# Generic_Electronics_Board_PCB_B.net
KiCad netlist of a schematic drawn in EAGLE
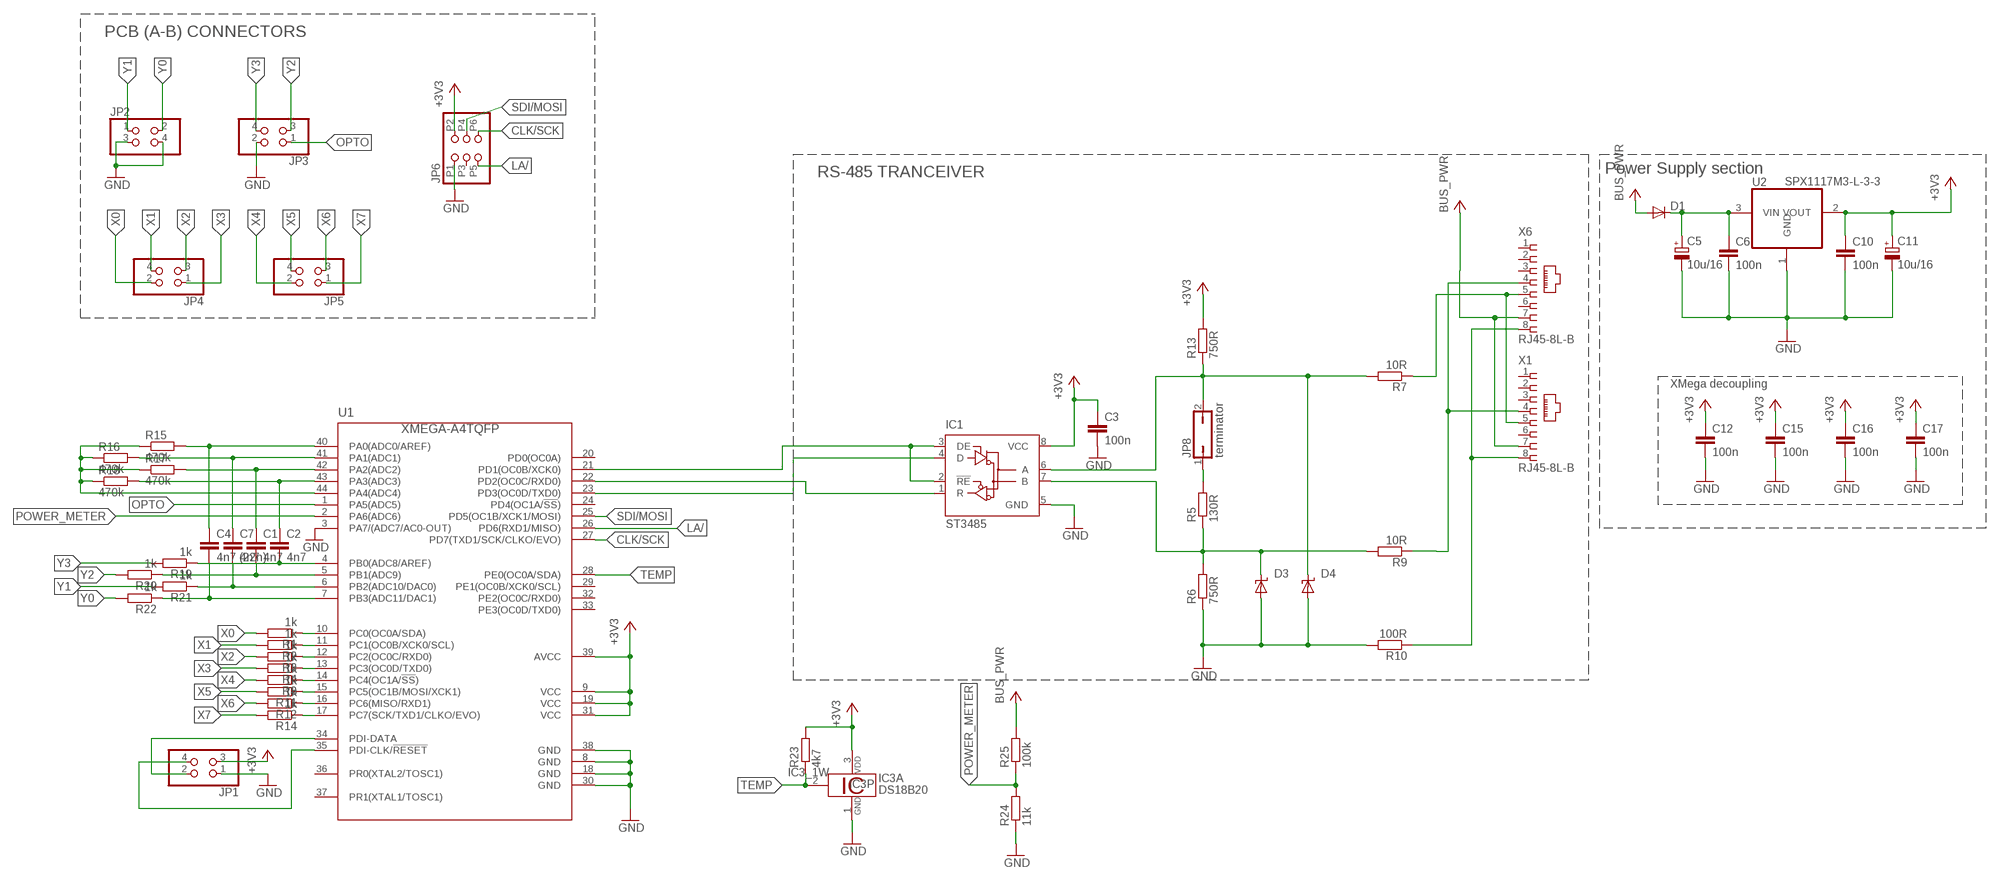
[diagram p0: schematic, sheet 1]

(export (version "E")
  (design (tool "Eeschema 10.0.6"))
  (components
    (comp (ref "C1")
      (value "4n7")
      (footprint "eagle-import:C0603")
      (libsource (lib "eagle-import") (part "C-EUC0603"))
    )
    (comp (ref "C2")
      (value "4n7")
      (footprint "eagle-import:C0603")
      (libsource (lib "eagle-import") (part "C-EUC0603"))
    )
    (comp (ref "C3")
      (value "100n")
      (footprint "eagle-import:C0603")
      (libsource (lib "eagle-import") (part "C-EUC0603"))
    )
    (comp (ref "C4")
      (value "4n7 (22n)")
      (footprint "eagle-import:C0603")
      (libsource (lib "eagle-import") (part "C-EUC0603"))
    )
    (comp (ref "C5")
      (value "10u/16")
      (footprint "eagle-import:SMC_C")
      (libsource (lib "eagle-import") (part "CPOL-EUSMCC"))
    )
    (comp (ref "C6")
      (value "100n")
      (footprint "eagle-import:C0603")
      (libsource (lib "eagle-import") (part "C-EUC0603"))
    )
    (comp (ref "C7")
      (value "4n7")
      (footprint "eagle-import:C0603")
      (libsource (lib "eagle-import") (part "C-EUC0603"))
    )
    (comp (ref "C10")
      (value "100n")
      (footprint "eagle-import:C0603")
      (libsource (lib "eagle-import") (part "C-EUC0603"))
    )
    (comp (ref "C11")
      (value "10u/16")
      (footprint "eagle-import:SMC_C")
      (libsource (lib "eagle-import") (part "CPOL-EUSMCC"))
    )
    (comp (ref "C12")
      (value "100n")
      (footprint "eagle-import:C0603")
      (libsource (lib "eagle-import") (part "C-EUC0603"))
    )
    (comp (ref "C15")
      (value "100n")
      (footprint "eagle-import:C0603")
      (libsource (lib "eagle-import") (part "C-EUC0603"))
    )
    (comp (ref "C16")
      (value "100n")
      (footprint "eagle-import:C0603")
      (libsource (lib "eagle-import") (part "C-EUC0603"))
    )
    (comp (ref "C17")
      (value "100n")
      (footprint "eagle-import:C0603")
      (libsource (lib "eagle-import") (part "C-EUC0603"))
    )
    (comp (ref "D1")
      (value "DIODE-DO-214AC")
      (footprint "eagle-import:DO-214AC")
      (libsource (lib "eagle-import") (part "DIODE-DO-214AC"))
    )
    (comp (ref "D3")
      (value "SUPPRESSOR-SMBJ")
      (footprint "eagle-import:SMBJ")
      (libsource (lib "eagle-import") (part "SUPPRESSOR-SMBJ"))
    )
    (comp (ref "D4")
      (value "SUPPRESSOR-SMBJ")
      (footprint "eagle-import:SMBJ")
      (libsource (lib "eagle-import") (part "SUPPRESSOR-SMBJ"))
    )
    (comp (ref "IC1")
      (value "ST3485")
      (footprint "eagle-import:D_R-PDSO-G8")
      (libsource (lib "eagle-import") (part "75176AD"))
    )
    (comp (ref "IC3")
      (value "DS18B20")
      (footprint "eagle-import:TO92-")
      (libsource (lib "eagle-import") (part "DS18B20"))
    )
    (comp (ref "JP1")
      (value "PINHD-2X2SMD")
      (footprint "eagle-import:2X2SMD")
      (libsource (lib "eagle-import") (part "PINHD-2X2SMD"))
    )
    (comp (ref "JP2")
      (value "PINHD-2X2")
      (footprint "eagle-import:2X02")
      (libsource (lib "eagle-import") (part "PINHD-2X2"))
    )
    (comp (ref "JP3")
      (value "PINHD-2X2")
      (footprint "eagle-import:2X02")
      (libsource (lib "eagle-import") (part "PINHD-2X2"))
    )
    (comp (ref "JP4")
      (value "PINHD-2X2")
      (footprint "eagle-import:2X02")
      (libsource (lib "eagle-import") (part "PINHD-2X2"))
    )
    (comp (ref "JP5")
      (value "PINHD-2X2")
      (footprint "eagle-import:2X02")
      (libsource (lib "eagle-import") (part "PINHD-2X2"))
    )
    (comp (ref "JP6")
      (value "PINHD-2X3SMD")
      (footprint "eagle-import:2X3SMD")
      (libsource (lib "eagle-import") (part "PINHD-2X3SMD"))
    )
    (comp (ref "JP8")
      (value "terminator")
      (footprint "eagle-import:JP1")
      (libsource (lib "eagle-import") (part "JP1Q"))
    )
    (comp (ref "R1")
      (value "1k")
      (footprint "eagle-import:R0603")
      (libsource (lib "eagle-import") (part "R-EU_R0603"))
    )
    (comp (ref "R2")
      (value "1k")
      (footprint "eagle-import:R0603")
      (libsource (lib "eagle-import") (part "R-EU_R0603"))
    )
    (comp (ref "R3")
      (value "1k")
      (footprint "eagle-import:R0603")
      (libsource (lib "eagle-import") (part "R-EU_R0603"))
    )
    (comp (ref "R4")
      (value "1k")
      (footprint "eagle-import:R0603")
      (libsource (lib "eagle-import") (part "R-EU_R0603"))
    )
    (comp (ref "R5")
      (value "130R")
      (footprint "eagle-import:R0603")
      (libsource (lib "eagle-import") (part "R-EU_R0603"))
    )
    (comp (ref "R6")
      (value "750R")
      (footprint "eagle-import:R0603")
      (libsource (lib "eagle-import") (part "R-EU_R0603"))
    )
    (comp (ref "R7")
      (value "10R")
      (footprint "eagle-import:R0603")
      (libsource (lib "eagle-import") (part "R-EU_R0603"))
    )
    (comp (ref "R8")
      (value "1k")
      (footprint "eagle-import:R0603")
      (libsource (lib "eagle-import") (part "R-EU_R0603"))
    )
    (comp (ref "R9")
      (value "10R")
      (footprint "eagle-import:R0603")
      (libsource (lib "eagle-import") (part "R-EU_R0603"))
    )
    (comp (ref "R10")
      (value "100R")
      (footprint "eagle-import:R0603")
      (libsource (lib "eagle-import") (part "R-EU_R0603"))
    )
    (comp (ref "R11")
      (value "1k")
      (footprint "eagle-import:R0603")
      (libsource (lib "eagle-import") (part "R-EU_R0603"))
    )
    (comp (ref "R12")
      (value "1k")
      (footprint "eagle-import:R0603")
      (libsource (lib "eagle-import") (part "R-EU_R0603"))
    )
    (comp (ref "R13")
      (value "750R")
      (footprint "eagle-import:R0603")
      (libsource (lib "eagle-import") (part "R-EU_R0603"))
    )
    (comp (ref "R14")
      (value "1k")
      (footprint "eagle-import:R0603")
      (libsource (lib "eagle-import") (part "R-EU_R0603"))
    )
    (comp (ref "R15")
      (value "470k")
      (footprint "eagle-import:R0603")
      (libsource (lib "eagle-import") (part "R-EU_R0603"))
    )
    (comp (ref "R16")
      (value "470k")
      (footprint "eagle-import:R0603")
      (libsource (lib "eagle-import") (part "R-EU_R0603"))
    )
    (comp (ref "R17")
      (value "470k")
      (footprint "eagle-import:R0603")
      (libsource (lib "eagle-import") (part "R-EU_R0603"))
    )
    (comp (ref "R18")
      (value "470k")
      (footprint "eagle-import:R0603")
      (libsource (lib "eagle-import") (part "R-EU_R0603"))
    )
    (comp (ref "R19")
      (value "1k")
      (footprint "eagle-import:R0603")
      (libsource (lib "eagle-import") (part "R-EU_R0603"))
    )
    (comp (ref "R20")
      (value "1k")
      (footprint "eagle-import:R0603")
      (libsource (lib "eagle-import") (part "R-EU_R0603"))
    )
    (comp (ref "R21")
      (value "1k")
      (footprint "eagle-import:R0603")
      (libsource (lib "eagle-import") (part "R-EU_R0603"))
    )
    (comp (ref "R22")
      (value "1k")
      (footprint "eagle-import:R0603")
      (libsource (lib "eagle-import") (part "R-EU_R0603"))
    )
    (comp (ref "R23")
      (value "4k7")
      (footprint "eagle-import:R0603")
      (libsource (lib "eagle-import") (part "R-EU_R0603"))
    )
    (comp (ref "R24")
      (value "11k")
      (footprint "eagle-import:R0603")
      (libsource (lib "eagle-import") (part "R-EU_R0603"))
    )
    (comp (ref "R25")
      (value "100k")
      (footprint "eagle-import:R0603")
      (libsource (lib "eagle-import") (part "R-EU_R0603"))
    )
    (comp (ref "U1")
      (value "XMEGA-A4TQFP")
      (footprint "eagle-import:TQFP44")
      (libsource (lib "eagle-import") (part "XMEGA-A4TQFP"))
    )
    (comp (ref "U2")
      (value "SPX1117M3-L-3-3")
      (footprint "eagle-import:SOT223")
      (fields (field (name "MPN") "REG1117"))
      (libsource (lib "eagle-import") (part "REG1117"))
    )
    (comp (ref "X1")
      (value "RJ45-8L-B")
      (footprint "eagle-import:RJ45-NO-SHIELD")
      (fields
        (field (name "MF") "TYCO ELECTRONICS")
        (field (name "MF_1") "TYCO ELECTRONICS")
        (field (name "MPN") "RJ45-8L-B")
        (field (name "OC_FARNELL") "1279843")
        (field (name "OC_NEWARK") "52K4445")
      )
      (libsource (lib "eagle-import") (part "RJ45-8L-B"))
    )
    (comp (ref "X6")
      (value "RJ45-8L-B")
      (footprint "eagle-import:RJ45-NO-SHIELD")
      (fields (field (name "MF") "TYCO ELECTRONICS"))
      (libsource (lib "eagle-import") (part "RJ45-8L-B"))
    )
  )
  (nets
    (net (code "1") (name "+3V3") (class "Default")
      (node (ref "C10") (pin "1") (pinfunction "1_1") (pintype "passive"))
      (node (ref "C11") (pin "+") (pinfunction "+_+") (pintype "passive"))
      (node (ref "C12") (pin "1") (pinfunction "1_1") (pintype "passive"))
      (node (ref "C15") (pin "1") (pinfunction "1_1") (pintype "passive"))
      (node (ref "C16") (pin "1") (pinfunction "1_1") (pintype "passive"))
      (node (ref "C17") (pin "1") (pinfunction "1_1") (pintype "passive"))
      (node (ref "C3") (pin "1") (pinfunction "1_1") (pintype "passive"))
      (node (ref "IC1") (pin "8") (pinfunction "VCC_8") (pintype "power_in"))
      (node (ref "IC3") (pin "3") (pinfunction "VDD_3") (pintype "power_in"))
      (node (ref "JP1") (pin "3") (pinfunction "3_3") (pintype "passive"))
      (node (ref "JP6") (pin "P2") (pinfunction "2_P2") (pintype "passive"))
      (node (ref "R13") (pin "2") (pinfunction "2_2") (pintype "passive"))
      (node (ref "R23") (pin "2") (pinfunction "2_2") (pintype "passive"))
      (node (ref "U1") (pin "19") (pinfunction "VCC_19") (pintype "power_in"))
      (node (ref "U1") (pin "31") (pinfunction "VCC_31") (pintype "power_in"))
      (node (ref "U1") (pin "39") (pinfunction "AVCC_39") (pintype "power_in"))
      (node (ref "U1") (pin "9") (pinfunction "VCC_9") (pintype "power_in"))
      (node (ref "U2") (pin "2") (pinfunction "VOUT_2") (pintype "output"))
    )
    (net (code "2") (name "BUS_PWR") (class "Default")
      (node (ref "D1") (pin "A") (pinfunction "A_A") (pintype "passive"))
      (node (ref "R25") (pin "2") (pinfunction "2_2") (pintype "passive"))
      (node (ref "X1") (pin "7") (pinfunction "7_7") (pintype "passive"))
      (node (ref "X6") (pin "7") (pinfunction "7_7") (pintype "passive"))
    )
    (net (code "3") (name "CLK{slash}SCK") (class "Default")
      (node (ref "JP6") (pin "P6") (pinfunction "6_P6") (pintype "passive"))
      (node (ref "U1") (pin "27") (pinfunction "PD7(TXD1/SCK/CLKO/EVO)_27") (pintype "bidirectional"))
    )
    (net (code "4") (name "GND") (class "Default")
      (node (ref "C10") (pin "2") (pinfunction "2_2") (pintype "passive"))
      (node (ref "C11") (pin "-") (pinfunction "-_-") (pintype "passive"))
      (node (ref "C12") (pin "2") (pinfunction "2_2") (pintype "passive"))
      (node (ref "C15") (pin "2") (pinfunction "2_2") (pintype "passive"))
      (node (ref "C16") (pin "2") (pinfunction "2_2") (pintype "passive"))
      (node (ref "C17") (pin "2") (pinfunction "2_2") (pintype "passive"))
      (node (ref "C3") (pin "2") (pinfunction "2_2") (pintype "passive"))
      (node (ref "C5") (pin "-") (pinfunction "-_-") (pintype "passive"))
      (node (ref "C6") (pin "2") (pinfunction "2_2") (pintype "passive"))
      (node (ref "D3") (pin "A") (pinfunction "A_A") (pintype "passive"))
      (node (ref "D4") (pin "A") (pinfunction "A_A") (pintype "passive"))
      (node (ref "IC1") (pin "5") (pinfunction "GND_5") (pintype "power_in"))
      (node (ref "IC3") (pin "1") (pinfunction "GND_1") (pintype "power_in"))
      (node (ref "JP1") (pin "1") (pinfunction "1_1") (pintype "passive"))
      (node (ref "JP2") (pin "3") (pinfunction "3_3") (pintype "passive"))
      (node (ref "JP2") (pin "4") (pinfunction "4_4") (pintype "passive"))
      (node (ref "JP3") (pin "2") (pinfunction "2_2") (pintype "passive"))
      (node (ref "JP6") (pin "P1") (pinfunction "1_P1") (pintype "passive"))
      (node (ref "R10") (pin "2") (pinfunction "2_2") (pintype "passive"))
      (node (ref "R24") (pin "1") (pinfunction "1_1") (pintype "passive"))
      (node (ref "R6") (pin "1") (pinfunction "1_1") (pintype "passive"))
      (node (ref "U1") (pin "18") (pinfunction "GND_18") (pintype "power_in"))
      (node (ref "U1") (pin "3") (pinfunction "PA7/(ADC7/AC0-OUT)_3") (pintype "bidirectional"))
      (node (ref "U1") (pin "30") (pinfunction "GND_30") (pintype "power_in"))
      (node (ref "U1") (pin "38") (pinfunction "GND_38") (pintype "power_in"))
      (node (ref "U1") (pin "8") (pinfunction "GND_8") (pintype "power_in"))
      (node (ref "U2") (pin "1") (pinfunction "GND_1") (pintype "power_in"))
    )
    (net (code "5") (name "LA{slash}") (class "Default")
      (node (ref "JP6") (pin "P5") (pinfunction "5_P5") (pintype "passive"))
      (node (ref "U1") (pin "26") (pinfunction "PD6(RXD1/MISO)_26") (pintype "bidirectional"))
    )
    (net (code "6") (name "Net-(IC1-A)") (class "Default")
      (node (ref "D4") (pin "C") (pinfunction "C_C") (pintype "passive"))
      (node (ref "IC1") (pin "6") (pinfunction "A_6") (pintype "output"))
      (node (ref "JP8") (pin "2") (pinfunction "2_2") (pintype "passive"))
      (node (ref "R13") (pin "1") (pinfunction "1_1") (pintype "passive"))
      (node (ref "R7") (pin "2") (pinfunction "2_2") (pintype "passive"))
    )
    (net (code "7") (name "Net-(IC1-B)") (class "Default")
      (node (ref "D3") (pin "C") (pinfunction "C_C") (pintype "passive"))
      (node (ref "IC1") (pin "7") (pinfunction "B_7") (pintype "output"))
      (node (ref "R5") (pin "1") (pinfunction "1_1") (pintype "passive"))
      (node (ref "R6") (pin "2") (pinfunction "2_2") (pintype "passive"))
      (node (ref "R9") (pin "2") (pinfunction "2_2") (pintype "passive"))
    )
    (net (code "8") (name "Net-(IC1-D)") (class "Default")
      (node (ref "IC1") (pin "4") (pinfunction "D_4") (pintype "input"))
      (node (ref "U1") (pin "23") (pinfunction "PD3(OC0D/TXD0)_23") (pintype "bidirectional"))
    )
    (net (code "9") (name "Net-(IC1-DE)") (class "Default")
      (node (ref "IC1") (pin "2") (pinfunction "~{RE}_2") (pintype "input"))
      (node (ref "IC1") (pin "3") (pinfunction "DE_3") (pintype "input"))
      (node (ref "U1") (pin "21") (pinfunction "PD1(OC0B/XCK0)_21") (pintype "bidirectional"))
    )
    (net (code "10") (name "Net-(IC1-R)") (class "Default")
      (node (ref "IC1") (pin "1") (pinfunction "R_1") (pintype "input"))
      (node (ref "U1") (pin "22") (pinfunction "PD2(OC0C/RXD0)_22") (pintype "bidirectional"))
    )
    (net (code "11") (name "Net-(JP8-Pad1)") (class "Default")
      (node (ref "JP8") (pin "1") (pinfunction "1_1") (pintype "passive"))
      (node (ref "R5") (pin "2") (pinfunction "2_2") (pintype "passive"))
    )
    (net (code "12") (name "Net-(R7-Pad1)") (class "Default")
      (node (ref "R7") (pin "1") (pinfunction "1_1") (pintype "passive"))
      (node (ref "X1") (pin "5") (pinfunction "5_5") (pintype "passive"))
      (node (ref "X6") (pin "5") (pinfunction "5_5") (pintype "passive"))
    )
    (net (code "13") (name "Net-(R9-Pad1)") (class "Default")
      (node (ref "R9") (pin "1") (pinfunction "1_1") (pintype "passive"))
      (node (ref "X1") (pin "4") (pinfunction "4_4") (pintype "passive"))
      (node (ref "X6") (pin "4") (pinfunction "4_4") (pintype "passive"))
    )
    (net (code "14") (name "Net-(R10-Pad1)") (class "Default")
      (node (ref "R10") (pin "1") (pinfunction "1_1") (pintype "passive"))
      (node (ref "X1") (pin "8") (pinfunction "8_8") (pintype "passive"))
      (node (ref "X6") (pin "8") (pinfunction "8_8") (pintype "passive"))
    )
    (net (code "15") (name "Net-(U1-PA0(ADC0{slash}AREF))") (class "Default")
      (node (ref "C4") (pin "1") (pinfunction "1_1") (pintype "passive"))
      (node (ref "R15") (pin "2") (pinfunction "2_2") (pintype "passive"))
      (node (ref "U1") (pin "40") (pinfunction "PA0(ADC0/AREF)_40") (pintype "bidirectional"))
    )
    (net (code "16") (name "Net-(U1-PA1(ADC1))") (class "Default")
      (node (ref "C7") (pin "1") (pinfunction "1_1") (pintype "passive"))
      (node (ref "R16") (pin "2") (pinfunction "2_2") (pintype "passive"))
      (node (ref "U1") (pin "41") (pinfunction "PA1(ADC1)_41") (pintype "bidirectional"))
    )
    (net (code "17") (name "Net-(U1-PA2(ADC2))") (class "Default")
      (node (ref "C1") (pin "1") (pinfunction "1_1") (pintype "passive"))
      (node (ref "R17") (pin "2") (pinfunction "2_2") (pintype "passive"))
      (node (ref "U1") (pin "42") (pinfunction "PA2(ADC2)_42") (pintype "bidirectional"))
    )
    (net (code "18") (name "Net-(U1-PA3(ADC3))") (class "Default")
      (node (ref "C2") (pin "1") (pinfunction "1_1") (pintype "passive"))
      (node (ref "R18") (pin "2") (pinfunction "2_2") (pintype "passive"))
      (node (ref "U1") (pin "43") (pinfunction "PA3(ADC3)_43") (pintype "bidirectional"))
    )
    (net (code "19") (name "Net-(U1-PA4(ADC4))") (class "Default")
      (node (ref "R15") (pin "1") (pinfunction "1_1") (pintype "passive"))
      (node (ref "R16") (pin "1") (pinfunction "1_1") (pintype "passive"))
      (node (ref "R17") (pin "1") (pinfunction "1_1") (pintype "passive"))
      (node (ref "R18") (pin "1") (pinfunction "1_1") (pintype "passive"))
      (node (ref "U1") (pin "44") (pinfunction "PA4(ADC4)_44") (pintype "bidirectional"))
    )
    (net (code "20") (name "Net-(U1-PB0(ADC8{slash}AREF))") (class "Default")
      (node (ref "C2") (pin "2") (pinfunction "2_2") (pintype "passive"))
      (node (ref "R19") (pin "1") (pinfunction "1_1") (pintype "passive"))
      (node (ref "U1") (pin "4") (pinfunction "PB0(ADC8/AREF)_4") (pintype "bidirectional"))
    )
    (net (code "21") (name "Net-(U1-PB1(ADC9))") (class "Default")
      (node (ref "C1") (pin "2") (pinfunction "2_2") (pintype "passive"))
      (node (ref "R20") (pin "1") (pinfunction "1_1") (pintype "passive"))
      (node (ref "U1") (pin "5") (pinfunction "PB1(ADC9)_5") (pintype "bidirectional"))
    )
    (net (code "22") (name "Net-(U1-PB2(ADC10{slash}DAC0))") (class "Default")
      (node (ref "C7") (pin "2") (pinfunction "2_2") (pintype "passive"))
      (node (ref "R21") (pin "1") (pinfunction "1_1") (pintype "passive"))
      (node (ref "U1") (pin "6") (pinfunction "PB2(ADC10/DAC0)_6") (pintype "bidirectional"))
    )
    (net (code "23") (name "Net-(U1-PB3(ADC11{slash}DAC1))") (class "Default")
      (node (ref "C4") (pin "2") (pinfunction "2_2") (pintype "passive"))
      (node (ref "R22") (pin "1") (pinfunction "1_1") (pintype "passive"))
      (node (ref "U1") (pin "7") (pinfunction "PB3(ADC11/DAC1)_7") (pintype "bidirectional"))
    )
    (net (code "24") (name "Net-(U1-PC0(OC0A{slash}SDA))") (class "Default")
      (node (ref "R1") (pin "1") (pinfunction "1_1") (pintype "passive"))
      (node (ref "U1") (pin "10") (pinfunction "PC0(OC0A/SDA)_10") (pintype "bidirectional"))
    )
    (net (code "25") (name "Net-(U1-PC1(OC0B{slash}XCK0{slash}SCL))") (class "Default")
      (node (ref "R2") (pin "1") (pinfunction "1_1") (pintype "passive"))
      (node (ref "U1") (pin "11") (pinfunction "PC1(OC0B/XCK0/SCL)_11") (pintype "bidirectional"))
    )
    (net (code "26") (name "Net-(U1-PC2(OC0C{slash}RXD0))") (class "Default")
      (node (ref "R3") (pin "1") (pinfunction "1_1") (pintype "passive"))
      (node (ref "U1") (pin "12") (pinfunction "PC2(OC0C/RXD0)_12") (pintype "bidirectional"))
    )
    (net (code "27") (name "Net-(U1-PC3(OC0D{slash}TXD0))") (class "Default")
      (node (ref "R4") (pin "1") (pinfunction "1_1") (pintype "passive"))
      (node (ref "U1") (pin "13") (pinfunction "PC3(OC0D/TXD0)_13") (pintype "bidirectional"))
    )
    (net (code "28") (name "Net-(U1-PC4(OC1A{slash}~{SS}))") (class "Default")
      (node (ref "R8") (pin "1") (pinfunction "1_1") (pintype "passive"))
      (node (ref "U1") (pin "14") (pinfunction "PC4(OC1A/~{SS})_14") (pintype "bidirectional"))
    )
    (net (code "29") (name "Net-(U1-PC5(OC1B{slash}MOSI{slash}XCK1))") (class "Default")
      (node (ref "R11") (pin "1") (pinfunction "1_1") (pintype "passive"))
      (node (ref "U1") (pin "15") (pinfunction "PC5(OC1B/MOSI/XCK1)_15") (pintype "bidirectional"))
    )
    (net (code "30") (name "Net-(U1-PC6(MISO{slash}RXD1))") (class "Default")
      (node (ref "R12") (pin "1") (pinfunction "1_1") (pintype "passive"))
      (node (ref "U1") (pin "16") (pinfunction "PC6(MISO/RXD1)_16") (pintype "bidirectional"))
    )
    (net (code "31") (name "Net-(U1-PC7(SCK{slash}TXD1{slash}CLKO{slash}EVO))") (class "Default")
      (node (ref "R14") (pin "1") (pinfunction "1_1") (pintype "passive"))
      (node (ref "U1") (pin "17") (pinfunction "PC7(SCK/TXD1/CLKO/EVO)_17") (pintype "bidirectional"))
    )
    (net (code "32") (name "Net-(U1-PDI-CLK{slash}~{RESET})") (class "Default")
      (node (ref "JP1") (pin "4") (pinfunction "4_4") (pintype "passive"))
      (node (ref "U1") (pin "35") (pinfunction "PDI-CLK/~{RESET}_35") (pintype "input"))
    )
    (net (code "33") (name "Net-(U1-PDI-DATA)") (class "Default")
      (node (ref "JP1") (pin "2") (pinfunction "2_2") (pintype "passive"))
      (node (ref "U1") (pin "34") (pinfunction "PDI-DATA_34") (pintype "bidirectional"))
    )
    (net (code "34") (name "Net-(U2-VIN)") (class "Default")
      (node (ref "C5") (pin "+") (pinfunction "+_+") (pintype "passive"))
      (node (ref "C6") (pin "1") (pinfunction "1_1") (pintype "passive"))
      (node (ref "D1") (pin "C") (pinfunction "C_C") (pintype "passive"))
      (node (ref "U2") (pin "3") (pinfunction "VIN_3") (pintype "input"))
    )
    (net (code "35") (name "OPTO") (class "Default")
      (node (ref "JP3") (pin "1") (pinfunction "1_1") (pintype "passive"))
      (node (ref "U1") (pin "1") (pinfunction "PA5(ADC5)_1") (pintype "bidirectional"))
    )
    (net (code "36") (name "POWER_METER") (class "Default")
      (node (ref "R24") (pin "2") (pinfunction "2_2") (pintype "passive"))
      (node (ref "R25") (pin "1") (pinfunction "1_1") (pintype "passive"))
      (node (ref "U1") (pin "2") (pinfunction "PA6(ADC6)_2") (pintype "bidirectional"))
    )
    (net (code "37") (name "SDI{slash}MOSI") (class "Default")
      (node (ref "JP6") (pin "P4") (pinfunction "4_P4") (pintype "passive"))
      (node (ref "U1") (pin "25") (pinfunction "PD5(OC1B/XCK1/MOSI)_25") (pintype "bidirectional"))
    )
    (net (code "38") (name "TEMP") (class "Default")
      (node (ref "IC3") (pin "2") (pinfunction "1W_2") (pintype "power_in"))
      (node (ref "R23") (pin "1") (pinfunction "1_1") (pintype "passive"))
      (node (ref "U1") (pin "28") (pinfunction "PE0(OC0A/SDA)_28") (pintype "bidirectional"))
    )
    (net (code "39") (name "X0") (class "Default")
      (node (ref "JP4") (pin "2") (pinfunction "2_2") (pintype "passive"))
      (node (ref "R1") (pin "2") (pinfunction "2_2") (pintype "passive"))
    )
    (net (code "40") (name "X1") (class "Default")
      (node (ref "JP4") (pin "4") (pinfunction "4_4") (pintype "passive"))
      (node (ref "R2") (pin "2") (pinfunction "2_2") (pintype "passive"))
    )
    (net (code "41") (name "X2") (class "Default")
      (node (ref "JP4") (pin "3") (pinfunction "3_3") (pintype "passive"))
      (node (ref "R3") (pin "2") (pinfunction "2_2") (pintype "passive"))
    )
    (net (code "42") (name "X3") (class "Default")
      (node (ref "JP4") (pin "1") (pinfunction "1_1") (pintype "passive"))
      (node (ref "R4") (pin "2") (pinfunction "2_2") (pintype "passive"))
    )
    (net (code "43") (name "X4") (class "Default")
      (node (ref "JP5") (pin "2") (pinfunction "2_2") (pintype "passive"))
      (node (ref "R8") (pin "2") (pinfunction "2_2") (pintype "passive"))
    )
    (net (code "44") (name "X5") (class "Default")
      (node (ref "JP5") (pin "4") (pinfunction "4_4") (pintype "passive"))
      (node (ref "R11") (pin "2") (pinfunction "2_2") (pintype "passive"))
    )
    (net (code "45") (name "X6") (class "Default")
      (node (ref "JP5") (pin "3") (pinfunction "3_3") (pintype "passive"))
      (node (ref "R12") (pin "2") (pinfunction "2_2") (pintype "passive"))
    )
    (net (code "46") (name "X7") (class "Default")
      (node (ref "JP5") (pin "1") (pinfunction "1_1") (pintype "passive"))
      (node (ref "R14") (pin "2") (pinfunction "2_2") (pintype "passive"))
    )
    (net (code "47") (name "Y0") (class "Default")
      (node (ref "JP2") (pin "2") (pinfunction "2_2") (pintype "passive"))
      (node (ref "R22") (pin "2") (pinfunction "2_2") (pintype "passive"))
    )
    (net (code "48") (name "Y1") (class "Default")
      (node (ref "JP2") (pin "1") (pinfunction "1_1") (pintype "passive"))
      (node (ref "R21") (pin "2") (pinfunction "2_2") (pintype "passive"))
    )
    (net (code "49") (name "Y2") (class "Default")
      (node (ref "JP3") (pin "3") (pinfunction "3_3") (pintype "passive"))
      (node (ref "R20") (pin "2") (pinfunction "2_2") (pintype "passive"))
    )
    (net (code "50") (name "Y3") (class "Default")
      (node (ref "JP3") (pin "4") (pinfunction "4_4") (pintype "passive"))
      (node (ref "R19") (pin "2") (pinfunction "2_2") (pintype "passive"))
    )
    (net (code "51") (name "unconnected-(JP6-3-PadP3)") (class "Default")
      (node (ref "JP6") (pin "P3") (pinfunction "3_P3") (pintype "passive"))
    )
    (net (code "52") (name "unconnected-(U1-PD0(OC0A)-Pad20)") (class "Default")
      (node (ref "U1") (pin "20") (pinfunction "PD0(OC0A)_20") (pintype "bidirectional"))
    )
    (net (code "53") (name "unconnected-(U1-PD4(OC1A{slash}~{SS})-Pad24)") (class "Default")
      (node (ref "U1") (pin "24") (pinfunction "PD4(OC1A/~{SS})_24") (pintype "bidirectional"))
    )
    (net (code "54") (name "unconnected-(U1-PE1(OC0B{slash}XCK0{slash}SCL)-Pad29)") (class "Default")
      (node (ref "U1") (pin "29") (pinfunction "PE1(OC0B/XCK0/SCL)_29") (pintype "bidirectional"))
    )
    (net (code "55") (name "unconnected-(U1-PE2(OC0C{slash}RXD0)-Pad32)") (class "Default")
      (node (ref "U1") (pin "32") (pinfunction "PE2(OC0C/RXD0)_32") (pintype "bidirectional"))
    )
    (net (code "56") (name "unconnected-(U1-PE3(OC0D{slash}TXD0)-Pad33)") (class "Default")
      (node (ref "U1") (pin "33") (pinfunction "PE3(OC0D/TXD0)_33") (pintype "bidirectional"))
    )
    (net (code "57") (name "unconnected-(U1-PR0(XTAL2{slash}TOSC1)-Pad36)") (class "Default")
      (node (ref "U1") (pin "36") (pinfunction "PR0(XTAL2/TOSC1)_36") (pintype "bidirectional"))
    )
    (net (code "58") (name "unconnected-(U1-PR1(XTAL1{slash}TOSC1)-Pad37)") (class "Default")
      (node (ref "U1") (pin "37") (pinfunction "PR1(XTAL1/TOSC1)_37") (pintype "bidirectional"))
    )
    (net (code "59") (name "unconnected-(X1-Pad1)") (class "Default")
      (node (ref "X1") (pin "1") (pinfunction "1_1") (pintype "passive"))
    )
    (net (code "60") (name "unconnected-(X1-Pad2)") (class "Default")
      (node (ref "X1") (pin "2") (pinfunction "2_2") (pintype "passive"))
    )
    (net (code "61") (name "unconnected-(X1-Pad3)") (class "Default")
      (node (ref "X1") (pin "3") (pinfunction "3_3") (pintype "passive"))
    )
    (net (code "62") (name "unconnected-(X1-Pad6)") (class "Default")
      (node (ref "X1") (pin "6") (pinfunction "6_6") (pintype "passive"))
    )
    (net (code "63") (name "unconnected-(X6-Pad1)") (class "Default")
      (node (ref "X6") (pin "1") (pinfunction "1_1") (pintype "passive"))
    )
    (net (code "64") (name "unconnected-(X6-Pad2)") (class "Default")
      (node (ref "X6") (pin "2") (pinfunction "2_2") (pintype "passive"))
    )
    (net (code "65") (name "unconnected-(X6-Pad3)") (class "Default")
      (node (ref "X6") (pin "3") (pinfunction "3_3") (pintype "passive"))
    )
    (net (code "66") (name "unconnected-(X6-Pad6)") (class "Default")
      (node (ref "X6") (pin "6") (pinfunction "6_6") (pintype "passive"))
    )
  )
)
